# Adafruit_DS3231_RTC_FeatherWing.net
KiCad netlist of a schematic drawn in EAGLE
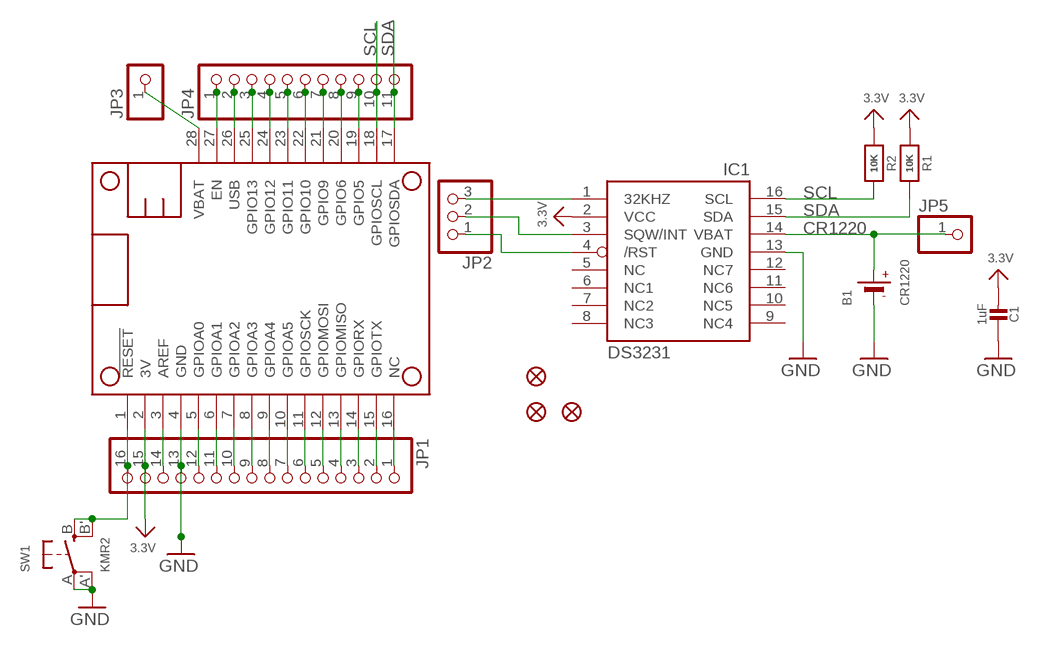
[diagram p0: schematic, sheet 1]

(export (version "E")
  (design (tool "Eeschema 10.0.6"))
  (components
    (comp (ref "B1")
      (value "CR1220")
      (footprint "eagle-import:CR1220-2")
      (libsource (lib "eagle-import") (part "BATTERYCR1220_2"))
    )
    (comp (ref "C1")
      (value "1uF")
      (footprint "eagle-import:0805-NO")
      (libsource (lib "eagle-import") (part "CAP_CERAMIC0805-NOOUTLINE"))
    )
    (comp (ref "FID1")
      (value "FIDUCIAL\"\"")
      (footprint "eagle-import:FIDUCIAL_1MM")
      (libsource (lib "eagle-import") (part "FIDUCIAL{dblquote}{dblquote}"))
    )
    (comp (ref "FID2")
      (value "FIDUCIAL\"\"")
      (footprint "eagle-import:FIDUCIAL_1MM")
      (libsource (lib "eagle-import") (part "FIDUCIAL{dblquote}{dblquote}"))
    )
    (comp (ref "FID3")
      (value "FIDUCIAL\"\"")
      (footprint "eagle-import:FIDUCIAL_1MM")
      (libsource (lib "eagle-import") (part "FIDUCIAL{dblquote}{dblquote}"))
    )
    (comp (ref "IC1")
      (value "DS3231/SO")
      (footprint "eagle-import:SO16W")
      (libsource (lib "eagle-import") (part "DS3231/SO"))
    )
    (comp (ref "JP1")
      (value "HEADER-1X16ROUND")
      (footprint "eagle-import:1X16_ROUND")
      (libsource (lib "eagle-import") (part "HEADER-1X16ROUND"))
    )
    (comp (ref "JP2")
      (value "HEADER-1X3ROUND")
      (footprint "eagle-import:1X03_ROUND")
      (libsource (lib "eagle-import") (part "HEADER-1X3ROUND"))
    )
    (comp (ref "JP3")
      (value "HEADER-1X1ROUND")
      (footprint "eagle-import:1X01_ROUND")
      (libsource (lib "eagle-import") (part "HEADER-1X1ROUND"))
    )
    (comp (ref "JP4")
      (value "HEADER-1X11")
      (footprint "eagle-import:1X11_ROUND")
      (libsource (lib "eagle-import") (part "HEADER-1X11"))
    )
    (comp (ref "JP5")
      (value "HEADER-1X1ROUND")
      (footprint "eagle-import:1X01_ROUND")
      (libsource (lib "eagle-import") (part "HEADER-1X1ROUND"))
    )
    (comp (ref "MS1")
      (value "MICROSHIELD_NODIM")
      (footprint "eagle-import:MICROSHIELD_DIM")
      (libsource (lib "eagle-import") (part "MICROSHIELD_NODIM"))
    )
    (comp (ref "R1")
      (value "10K")
      (footprint "eagle-import:0805-NO")
      (libsource (lib "eagle-import") (part "RESISTOR0805_NOOUTLINE"))
    )
    (comp (ref "R2")
      (value "10K")
      (footprint "eagle-import:0805-NO")
      (libsource (lib "eagle-import") (part "RESISTOR0805_NOOUTLINE"))
    )
    (comp (ref "SW1")
      (value "KMR2")
      (footprint "eagle-import:BTN_KMR2_4.6X2.8")
      (libsource (lib "eagle-import") (part "SWITCH_TACT_SMT4.6X2.8"))
    )
  )
  (nets
    (net (code "1") (name "/CR1220") (class "Default")
      (node (ref "B1") (pin "+") (pinfunction "+_+") (pintype "passive"))
      (node (ref "IC1") (pin "14") (pinfunction "VBAT_14") (pintype "power_in"))
      (node (ref "JP5") (pin "1") (pinfunction "1_1") (pintype "passive"))
    )
    (net (code "2") (name "/SCL") (class "Default")
      (node (ref "IC1") (pin "16") (pinfunction "SCL_16") (pintype "bidirectional"))
      (node (ref "JP4") (pin "10") (pinfunction "10_10") (pintype "passive"))
      (node (ref "MS1") (pin "18") (pinfunction "GPIOSCL_18") (pintype "bidirectional"))
      (node (ref "R2") (pin "2") (pinfunction "2_2") (pintype "passive"))
    )
    (net (code "3") (name "/SDA") (class "Default")
      (node (ref "IC1") (pin "15") (pinfunction "SDA_15") (pintype "bidirectional"))
      (node (ref "JP4") (pin "11") (pinfunction "11_11") (pintype "passive"))
      (node (ref "MS1") (pin "17") (pinfunction "GPIOSDA_17") (pintype "bidirectional"))
      (node (ref "R1") (pin "2") (pinfunction "2_2") (pintype "passive"))
    )
    (net (code "4") (name "3.3V") (class "Default")
      (node (ref "C1") (pin "2") (pinfunction "2_2") (pintype "passive"))
      (node (ref "IC1") (pin "2") (pinfunction "VCC_2") (pintype "power_in"))
      (node (ref "JP1") (pin "15") (pinfunction "15_15") (pintype "passive"))
      (node (ref "MS1") (pin "2") (pinfunction "3V_2") (pintype "power_in"))
      (node (ref "R1") (pin "1") (pinfunction "1_1") (pintype "passive"))
      (node (ref "R2") (pin "1") (pinfunction "1_1") (pintype "passive"))
    )
    (net (code "5") (name "GND") (class "Default")
      (node (ref "B1") (pin "-") (pinfunction "-_-") (pintype "passive"))
      (node (ref "C1") (pin "1") (pinfunction "1_1") (pintype "passive"))
      (node (ref "IC1") (pin "13") (pinfunction "GND_13") (pintype "power_in"))
      (node (ref "JP1") (pin "13") (pinfunction "13_13") (pintype "passive"))
      (node (ref "MS1") (pin "4") (pinfunction "GND_4") (pintype "power_in"))
      (node (ref "SW1") (pin "A") (pinfunction "P_A") (pintype "passive"))
      (node (ref "SW1") (pin "A'") (pinfunction "P1_A'") (pintype "passive"))
    )
    (net (code "6") (name "Net-(IC1-32KHZ)") (class "Default")
      (node (ref "IC1") (pin "1") (pinfunction "32KHZ_1") (pintype "output"))
      (node (ref "JP2") (pin "3") (pinfunction "3_3") (pintype "passive"))
    )
    (net (code "7") (name "Net-(IC1-SQW{slash}INT)") (class "Default")
      (node (ref "IC1") (pin "3") (pinfunction "SQW/INT_3") (pintype "output"))
      (node (ref "JP2") (pin "2") (pinfunction "2_2") (pintype "passive"))
    )
    (net (code "8") (name "Net-(IC1-{slash}RST)") (class "Default")
      (node (ref "IC1") (pin "4") (pinfunction "/RST_4") (pintype "passive"))
      (node (ref "JP2") (pin "1") (pinfunction "1_1") (pintype "passive"))
    )
    (net (code "9") (name "Net-(MS1-AREF)") (class "Default")
      (node (ref "JP1") (pin "14") (pinfunction "14_14") (pintype "passive"))
      (node (ref "MS1") (pin "3") (pinfunction "AREF_3") (pintype "passive"))
    )
    (net (code "10") (name "Net-(MS1-EN)") (class "Default")
      (node (ref "JP4") (pin "1") (pinfunction "1_1") (pintype "passive"))
      (node (ref "MS1") (pin "27") (pinfunction "EN_27") (pintype "passive"))
    )
    (net (code "11") (name "Net-(MS1-GPIO5)") (class "Default")
      (node (ref "JP4") (pin "9") (pinfunction "9_9") (pintype "passive"))
      (node (ref "MS1") (pin "19") (pinfunction "GPIO5_19") (pintype "bidirectional"))
    )
    (net (code "12") (name "Net-(MS1-GPIO6)") (class "Default")
      (node (ref "JP4") (pin "8") (pinfunction "8_8") (pintype "passive"))
      (node (ref "MS1") (pin "20") (pinfunction "GPIO6_20") (pintype "bidirectional"))
    )
    (net (code "13") (name "Net-(MS1-GPIO9)") (class "Default")
      (node (ref "JP4") (pin "7") (pinfunction "7_7") (pintype "passive"))
      (node (ref "MS1") (pin "21") (pinfunction "GPIO9_21") (pintype "bidirectional"))
    )
    (net (code "14") (name "Net-(MS1-GPIO10)") (class "Default")
      (node (ref "JP4") (pin "6") (pinfunction "6_6") (pintype "passive"))
      (node (ref "MS1") (pin "22") (pinfunction "GPIO10_22") (pintype "bidirectional"))
    )
    (net (code "15") (name "Net-(MS1-GPIO11)") (class "Default")
      (node (ref "JP4") (pin "5") (pinfunction "5_5") (pintype "passive"))
      (node (ref "MS1") (pin "23") (pinfunction "GPIO11_23") (pintype "bidirectional"))
    )
    (net (code "16") (name "Net-(MS1-GPIO12)") (class "Default")
      (node (ref "JP4") (pin "4") (pinfunction "4_4") (pintype "passive"))
      (node (ref "MS1") (pin "24") (pinfunction "GPIO12_24") (pintype "bidirectional"))
    )
    (net (code "17") (name "Net-(MS1-GPIO13)") (class "Default")
      (node (ref "JP4") (pin "3") (pinfunction "3_3") (pintype "passive"))
      (node (ref "MS1") (pin "25") (pinfunction "GPIO13_25") (pintype "bidirectional"))
    )
    (net (code "18") (name "Net-(MS1-GPIOA0)") (class "Default")
      (node (ref "JP1") (pin "12") (pinfunction "12_12") (pintype "passive"))
      (node (ref "MS1") (pin "5") (pinfunction "GPIOA0_5") (pintype "bidirectional"))
    )
    (net (code "19") (name "Net-(MS1-GPIOA1)") (class "Default")
      (node (ref "JP1") (pin "11") (pinfunction "11_11") (pintype "passive"))
      (node (ref "MS1") (pin "6") (pinfunction "GPIOA1_6") (pintype "bidirectional"))
    )
    (net (code "20") (name "Net-(MS1-GPIOA2)") (class "Default")
      (node (ref "JP1") (pin "10") (pinfunction "10_10") (pintype "passive"))
      (node (ref "MS1") (pin "7") (pinfunction "GPIOA2_7") (pintype "bidirectional"))
    )
    (net (code "21") (name "Net-(MS1-GPIOA3)") (class "Default")
      (node (ref "JP1") (pin "9") (pinfunction "9_9") (pintype "passive"))
      (node (ref "MS1") (pin "8") (pinfunction "GPIOA3_8") (pintype "bidirectional"))
    )
    (net (code "22") (name "Net-(MS1-GPIOA4)") (class "Default")
      (node (ref "JP1") (pin "8") (pinfunction "8_8") (pintype "passive"))
      (node (ref "MS1") (pin "9") (pinfunction "GPIOA4_9") (pintype "bidirectional"))
    )
    (net (code "23") (name "Net-(MS1-GPIOA5)") (class "Default")
      (node (ref "JP1") (pin "7") (pinfunction "7_7") (pintype "passive"))
      (node (ref "MS1") (pin "10") (pinfunction "GPIOA5_10") (pintype "bidirectional"))
    )
    (net (code "24") (name "Net-(MS1-GPIOMISO)") (class "Default")
      (node (ref "JP1") (pin "4") (pinfunction "4_4") (pintype "passive"))
      (node (ref "MS1") (pin "13") (pinfunction "GPIOMISO_13") (pintype "bidirectional"))
    )
    (net (code "25") (name "Net-(MS1-GPIOMOSI)") (class "Default")
      (node (ref "JP1") (pin "5") (pinfunction "5_5") (pintype "passive"))
      (node (ref "MS1") (pin "12") (pinfunction "GPIOMOSI_12") (pintype "bidirectional"))
    )
    (net (code "26") (name "Net-(MS1-GPIORX)") (class "Default")
      (node (ref "JP1") (pin "3") (pinfunction "3_3") (pintype "passive"))
      (node (ref "MS1") (pin "14") (pinfunction "GPIORX_14") (pintype "bidirectional"))
    )
    (net (code "27") (name "Net-(MS1-GPIOSCK)") (class "Default")
      (node (ref "JP1") (pin "6") (pinfunction "6_6") (pintype "passive"))
      (node (ref "MS1") (pin "11") (pinfunction "GPIOSCK_11") (pintype "bidirectional"))
    )
    (net (code "28") (name "Net-(MS1-GPIOTX)") (class "Default")
      (node (ref "JP1") (pin "2") (pinfunction "2_2") (pintype "passive"))
      (node (ref "MS1") (pin "15") (pinfunction "GPIOTX_15") (pintype "bidirectional"))
    )
    (net (code "29") (name "Net-(MS1-NC)") (class "Default")
      (node (ref "JP1") (pin "1") (pinfunction "1_1") (pintype "passive"))
      (node (ref "MS1") (pin "16") (pinfunction "NC_16") (pintype "passive"))
    )
    (net (code "30") (name "Net-(MS1-USB)") (class "Default")
      (node (ref "JP4") (pin "2") (pinfunction "2_2") (pintype "passive"))
      (node (ref "MS1") (pin "26") (pinfunction "USB_26") (pintype "power_in"))
    )
    (net (code "31") (name "Net-(MS1-VBAT)") (class "Default")
      (node (ref "JP3") (pin "1") (pinfunction "1_1") (pintype "passive"))
      (node (ref "MS1") (pin "28") (pinfunction "VBAT_28") (pintype "power_in"))
    )
    (net (code "32") (name "Net-(MS1-~{RESET})") (class "Default")
      (node (ref "JP1") (pin "16") (pinfunction "16_16") (pintype "passive"))
      (node (ref "MS1") (pin "1") (pinfunction "~{RESET}_1") (pintype "input"))
      (node (ref "SW1") (pin "B") (pinfunction "S_B") (pintype "passive"))
      (node (ref "SW1") (pin "B'") (pinfunction "S1_B'") (pintype "passive"))
    )
    (net (code "33") (name "unconnected-(IC1-NC-Pad5)") (class "Default")
      (node (ref "IC1") (pin "5") (pinfunction "NC_5") (pintype "no_connect"))
    )
    (net (code "34") (name "unconnected-(IC1-NC1-Pad6)") (class "Default")
      (node (ref "IC1") (pin "6") (pinfunction "NC1_6") (pintype "no_connect"))
    )
    (net (code "35") (name "unconnected-(IC1-NC2-Pad7)") (class "Default")
      (node (ref "IC1") (pin "7") (pinfunction "NC2_7") (pintype "no_connect"))
    )
    (net (code "36") (name "unconnected-(IC1-NC3-Pad8)") (class "Default")
      (node (ref "IC1") (pin "8") (pinfunction "NC3_8") (pintype "no_connect"))
    )
    (net (code "37") (name "unconnected-(IC1-NC4-Pad9)") (class "Default")
      (node (ref "IC1") (pin "9") (pinfunction "NC4_9") (pintype "no_connect"))
    )
    (net (code "38") (name "unconnected-(IC1-NC5-Pad10)") (class "Default")
      (node (ref "IC1") (pin "10") (pinfunction "NC5_10") (pintype "no_connect"))
    )
    (net (code "39") (name "unconnected-(IC1-NC6-Pad11)") (class "Default")
      (node (ref "IC1") (pin "11") (pinfunction "NC6_11") (pintype "no_connect"))
    )
    (net (code "40") (name "unconnected-(IC1-NC7-Pad12)") (class "Default")
      (node (ref "IC1") (pin "12") (pinfunction "NC7_12") (pintype "no_connect"))
    )
  )
)
